# b2b_connector.net
KiCad netlist of a schematic drawn in Altium Designer
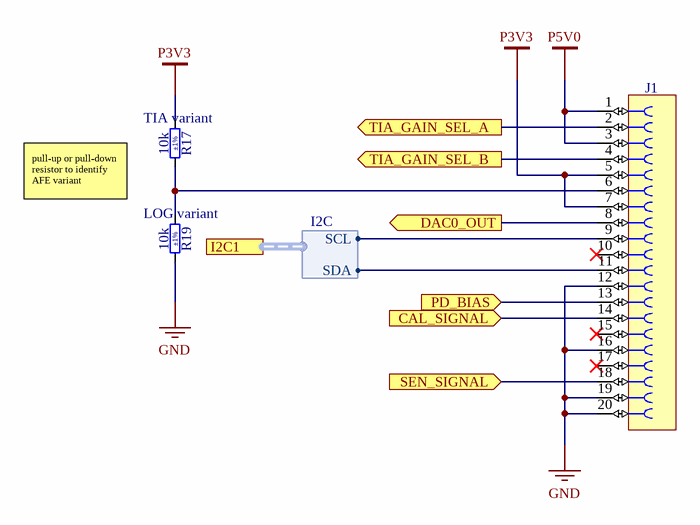
[diagram p0: b2b_connector.SchDoc]

(export (version "E")
  (design (tool "Eeschema 10.0.6"))
  (components
    (comp (ref "J1")
      (value "SlimStack™")
      (footprint "MOLEX_52991-0208")
      (description "Connector 20 Female")
      (fields
        (field (name "PART NUMBER") "MOLEX_52991-0208")
        (field (name "MANUFACTURER") "MOLEX")
        (field (name "AUTHOR") "CERN DEM BC")
      )
      (libsource (lib "Connectors") (part "Connector 20 Female"))
    )
    (comp (ref "R17")
      (value "10k")
      (footprint "RESC1005X40N")
      (description "Resistor - 1%")
      (fields
        (field (name "TOLERANCE") "±1%")
        (field (name "PART NUMBER") "R0402_10K_1%_0.0625W_100PPM")
        (field (name "POWER") "0.0625W")
        (field (name "AUTHOR") "CERN DEM JLC")
      )
      (libsource (lib "Resistors") (part "Resistor - 1%"))
    )
    (comp (ref "R19")
      (value "10k")
      (footprint "RESC1005X40N")
      (description "Resistor - 1%")
      (fields
        (field (name "TOLERANCE") "±1%")
        (field (name "PART NUMBER") "R0402_10K_1%_0.0625W_100PPM")
        (field (name "POWER") "0.0625W")
        (field (name "AUTHOR") "CERN DEM JLC")
      )
      (libsource (lib "Resistors") (part "Resistor - 1%"))
    )
  )
  (nets
    (net (code "2") (name "/CAL_SIGNAL") (class "Default")
      (node (ref "J1") (pin "14") (pinfunction "14_14") (pintype "bidirectional"))
    )
    (net (code "3") (name "/DAC0_OUT") (class "Default")
      (node (ref "J1") (pin "8") (pinfunction "8_8") (pintype "bidirectional"))
    )
    (net (code "4") (name "/PD_BIAS") (class "Default")
      (node (ref "J1") (pin "13") (pinfunction "13_13") (pintype "bidirectional"))
    )
    (net (code "5") (name "/SCL") (class "Default")
      (node (ref "J1") (pin "9") (pinfunction "9_9") (pintype "bidirectional"))
    )
    (net (code "6") (name "/SDA") (class "Default")
      (node (ref "J1") (pin "11") (pinfunction "11_11") (pintype "bidirectional"))
    )
    (net (code "7") (name "/SEN_SIGNAL") (class "Default")
      (node (ref "J1") (pin "18") (pinfunction "18_18") (pintype "bidirectional"))
    )
    (net (code "8") (name "/TIA_GAIN_SEL_A") (class "Default")
      (node (ref "J1") (pin "2") (pinfunction "2_2") (pintype "bidirectional"))
    )
    (net (code "9") (name "/TIA_GAIN_SEL_B") (class "Default")
      (node (ref "J1") (pin "4") (pinfunction "4_4") (pintype "bidirectional"))
    )
    (net (code "11") (name "GND") (class "Default")
      (node (ref "J1") (pin "12") (pinfunction "12_12") (pintype "bidirectional"))
      (node (ref "J1") (pin "16") (pinfunction "16_16") (pintype "bidirectional"))
      (node (ref "J1") (pin "19") (pinfunction "19_19") (pintype "bidirectional"))
      (node (ref "J1") (pin "20") (pinfunction "20_20") (pintype "bidirectional"))
      (node (ref "R19") (pin "1") (pinfunction "1_1") (pintype "passive"))
    )
    (net (code "12") (name "Net-(J1-Pad6)") (class "Default")
      (node (ref "J1") (pin "6") (pinfunction "6_6") (pintype "bidirectional"))
      (node (ref "R17") (pin "1") (pinfunction "1_1") (pintype "passive"))
      (node (ref "R19") (pin "2") (pinfunction "2_2") (pintype "passive"))
    )
    (net (code "13") (name "P3V3") (class "Default")
      (node (ref "J1") (pin "5") (pinfunction "5_5") (pintype "bidirectional"))
      (node (ref "J1") (pin "7") (pinfunction "7_7") (pintype "bidirectional"))
      (node (ref "R17") (pin "2") (pinfunction "2_2") (pintype "passive"))
    )
    (net (code "14") (name "P5V0") (class "Default")
      (node (ref "J1") (pin "1") (pinfunction "1_1") (pintype "bidirectional"))
      (node (ref "J1") (pin "3") (pinfunction "3_3") (pintype "bidirectional"))
    )
    (net (code "15") (name "unconnected-(J1-Pad10)") (class "Default")
      (node (ref "J1") (pin "10") (pinfunction "10_10") (pintype "bidirectional+no_connect"))
    )
    (net (code "16") (name "unconnected-(J1-Pad15)") (class "Default")
      (node (ref "J1") (pin "15") (pinfunction "15_15") (pintype "bidirectional+no_connect"))
    )
    (net (code "17") (name "unconnected-(J1-Pad17)") (class "Default")
      (node (ref "J1") (pin "17") (pinfunction "17_17") (pintype "bidirectional+no_connect"))
    )
  )
)
